# Alternative2.net
KiCad netlist of a schematic drawn in EAGLE
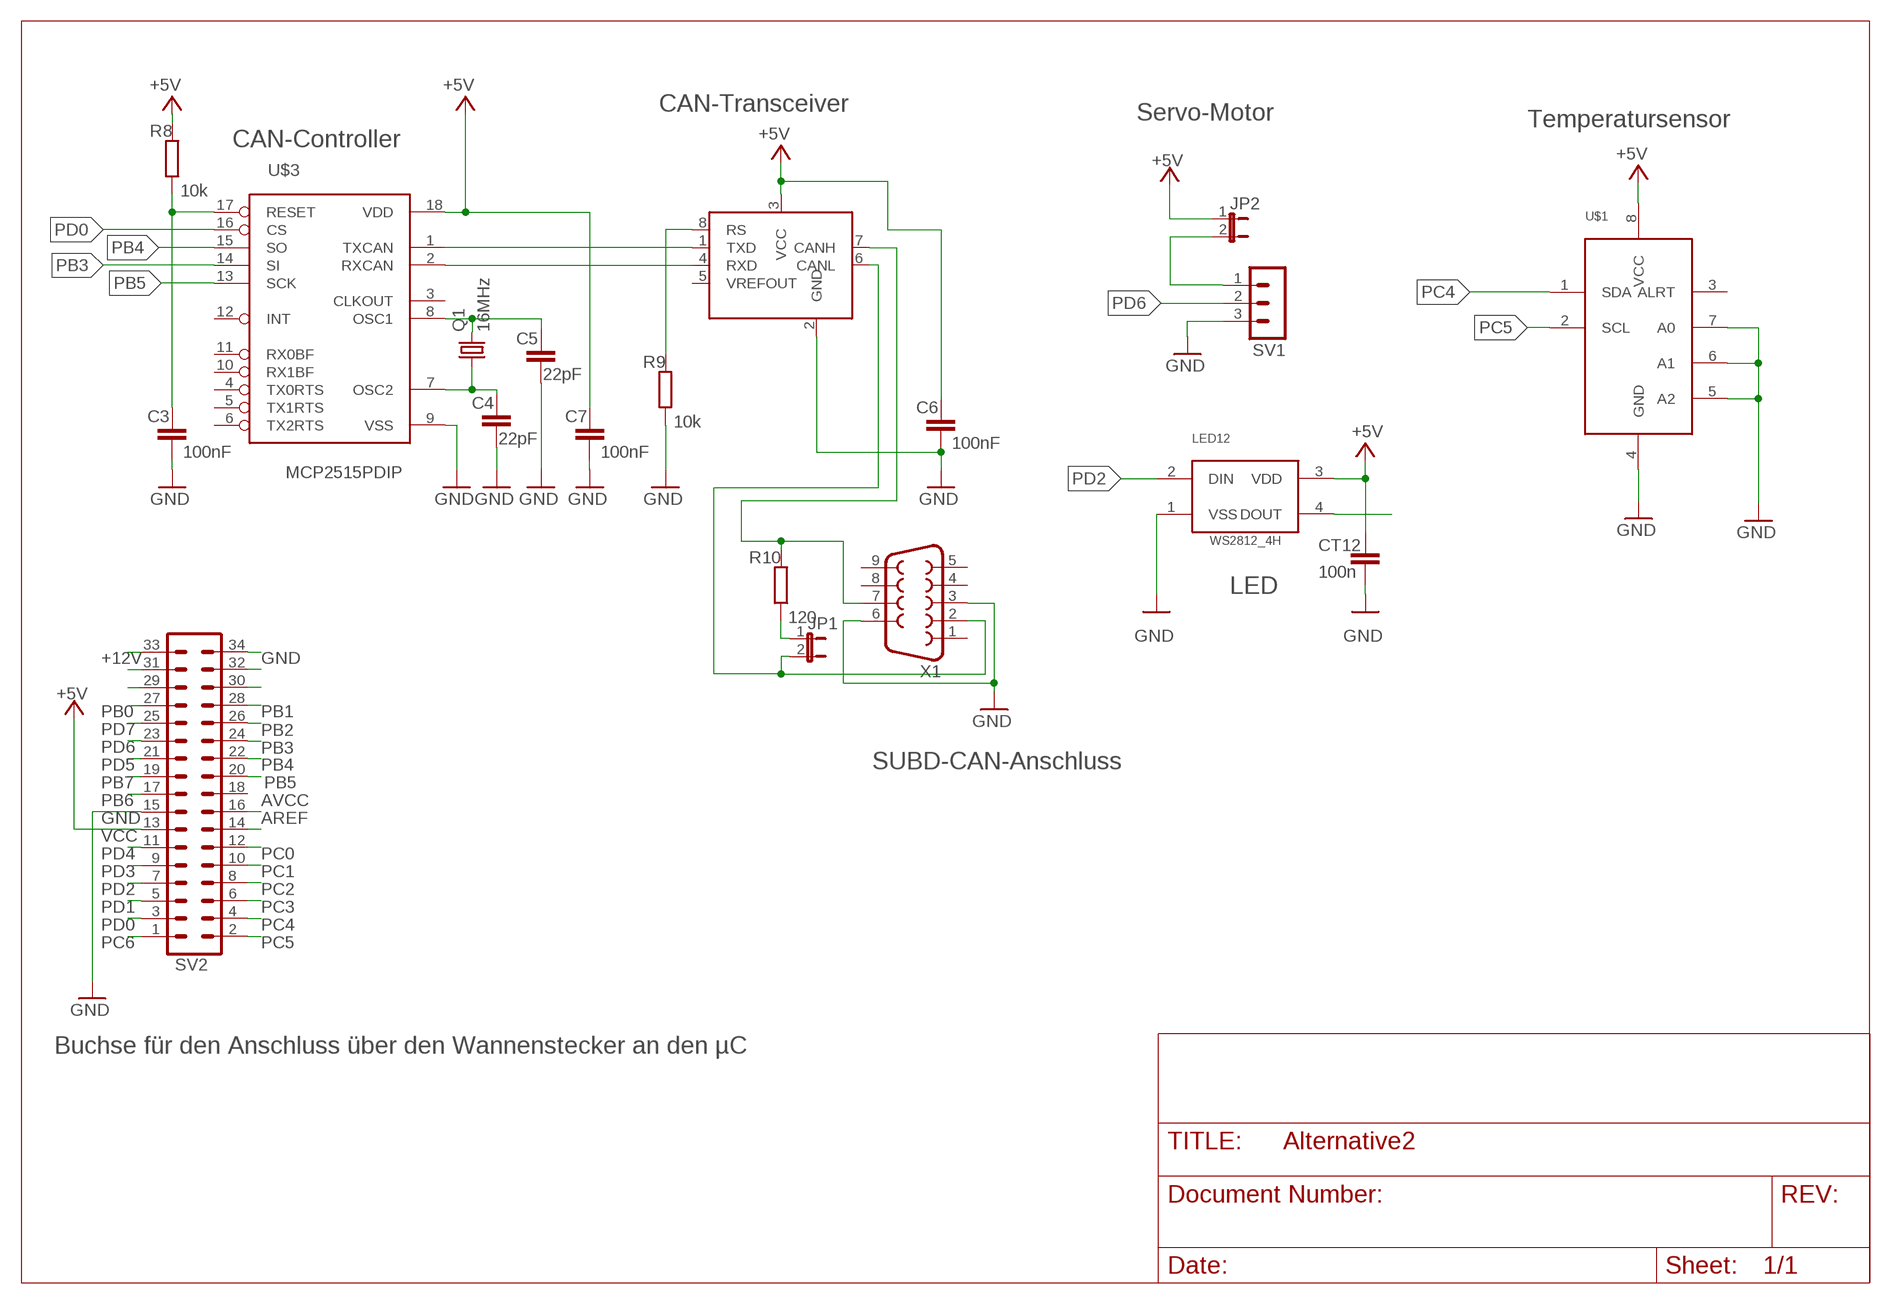
[diagram p0: schematic, sheet 1]

(export (version "E")
  (design (tool "Eeschema 10.0.6"))
  (components
    (comp (ref "C3")
      (value "100nF")
      (footprint "eagle-import:C0805K")
      (libsource (lib "eagle-import") (part "C-EUC0805K"))
    )
    (comp (ref "C4")
      (value "22pF")
      (footprint "eagle-import:C0805K")
      (libsource (lib "eagle-import") (part "C-EUC0805K"))
    )
    (comp (ref "C5")
      (value "22pF")
      (footprint "eagle-import:C0805K")
      (libsource (lib "eagle-import") (part "C-EUC0805K"))
    )
    (comp (ref "C6")
      (value "100nF")
      (footprint "eagle-import:C0805K")
      (libsource (lib "eagle-import") (part "C-EUC0805K"))
    )
    (comp (ref "C7")
      (value "100nF")
      (footprint "eagle-import:C0805K")
      (libsource (lib "eagle-import") (part "C-EUC0805K"))
    )
    (comp (ref "CT12")
      (value "100n")
      (footprint "eagle-import:C0805")
      (libsource (lib "eagle-import") (part "C-EUC0805"))
    )
    (comp (ref "IC2")
      (value "PCA82C251")
      (footprint "eagle-import:SO8")
      (libsource (lib "eagle-import") (part "82C250SMDSMD"))
    )
    (comp (ref "JP1")
      (value "JP1E")
      (footprint "eagle-import:JP1")
      (libsource (lib "eagle-import") (part "JP1E"))
    )
    (comp (ref "JP2")
      (value "JP1E")
      (footprint "eagle-import:JP1")
      (libsource (lib "eagle-import") (part "JP1E"))
    )
    (comp (ref "LED12")
      (value "WS2812_4H")
      (footprint "eagle-import:WS2812_4")
      (libsource (lib "eagle-import") (part "WS2812_4H"))
    )
    (comp (ref "Q1")
      (value "16MHz")
      (footprint "eagle-import:HC49_S")
      (libsource (lib "eagle-import") (part "CRYSTALHC49S"))
    )
    (comp (ref "R8")
      (value "10k")
      (footprint "eagle-import:R0805")
      (libsource (lib "eagle-import") (part "R-EU_R0805"))
    )
    (comp (ref "R9")
      (value "10k")
      (footprint "eagle-import:R0805")
      (libsource (lib "eagle-import") (part "R-EU_R0805"))
    )
    (comp (ref "R10")
      (value "120")
      (footprint "eagle-import:R0805")
      (libsource (lib "eagle-import") (part "R-EU_R0805"))
    )
    (comp (ref "SV1")
      (value "MA03-1")
      (footprint "eagle-import:MA03-1")
      (libsource (lib "eagle-import") (part "MA03-1"))
    )
    (comp (ref "SV2")
      (value "ML34")
      (footprint "eagle-import:ML34")
      (libsource (lib "eagle-import") (part "ML34"))
    )
    (comp (ref "U$1")
      (value "TMP75-SO8")
      (footprint "eagle-import:SO08")
      (libsource (lib "eagle-import") (part "TMP75-SO8"))
    )
    (comp (ref "U$3")
      (value "MCP2515PDIP")
      (footprint "eagle-import:DIL18")
      (libsource (lib "eagle-import") (part "MCP2515PDIP"))
    )
    (comp (ref "X1")
      (value "F09HP")
      (footprint "eagle-import:F09HP")
      (libsource (lib "eagle-import") (part "F09HP"))
    )
  )
  (nets
    (net (code "1") (name "+5V") (class "Default")
      (node (ref "C6") (pin "1") (pinfunction "1_1") (pintype "passive"))
      (node (ref "C7") (pin "1") (pinfunction "1_1") (pintype "passive"))
      (node (ref "CT12") (pin "1") (pinfunction "1_1") (pintype "passive"))
      (node (ref "IC2") (pin "3") (pinfunction "VCC_3") (pintype "power_in"))
      (node (ref "JP2") (pin "1") (pinfunction "1_1") (pintype "passive"))
      (node (ref "LED12") (pin "3") (pinfunction "VDD_3") (pintype "power_in"))
      (node (ref "R8") (pin "2") (pinfunction "2_2") (pintype "passive"))
      (node (ref "SV2") (pin "13") (pinfunction "13_13") (pintype "passive"))
      (node (ref "U$1") (pin "8") (pinfunction "VCC_8") (pintype "power_in"))
      (node (ref "U$3") (pin "18") (pinfunction "VDD_18") (pintype "power_in"))
    )
    (net (code "2") (name "/+12V") (class "Default")
      (node (ref "SV2") (pin "33") (pinfunction "33_33") (pintype "passive"))
    )
    (net (code "3") (name "/AREF") (class "Default")
      (node (ref "SV2") (pin "16") (pinfunction "16_16") (pintype "passive"))
    )
    (net (code "4") (name "/PB0") (class "Default")
      (node (ref "SV2") (pin "27") (pinfunction "27_27") (pintype "passive"))
    )
    (net (code "5") (name "/PB1") (class "Default")
      (node (ref "SV2") (pin "28") (pinfunction "28_28") (pintype "passive"))
    )
    (net (code "6") (name "/PB2") (class "Default")
      (node (ref "SV2") (pin "26") (pinfunction "26_26") (pintype "passive"))
    )
    (net (code "7") (name "/PB6") (class "Default")
      (node (ref "SV2") (pin "17") (pinfunction "17_17") (pintype "passive"))
    )
    (net (code "8") (name "/PB7") (class "Default")
      (node (ref "SV2") (pin "19") (pinfunction "19_19") (pintype "passive"))
    )
    (net (code "9") (name "/PC0") (class "Default")
      (node (ref "SV2") (pin "12") (pinfunction "12_12") (pintype "passive"))
    )
    (net (code "10") (name "/PC1") (class "Default")
      (node (ref "SV2") (pin "10") (pinfunction "10_10") (pintype "passive"))
    )
    (net (code "11") (name "/PC2") (class "Default")
      (node (ref "SV2") (pin "8") (pinfunction "8_8") (pintype "passive"))
    )
    (net (code "12") (name "/PC3") (class "Default")
      (node (ref "SV2") (pin "6") (pinfunction "6_6") (pintype "passive"))
    )
    (net (code "13") (name "/PC6") (class "Default")
      (node (ref "SV2") (pin "1") (pinfunction "1_1") (pintype "passive"))
    )
    (net (code "14") (name "/PD1") (class "Default")
      (node (ref "SV2") (pin "5") (pinfunction "5_5") (pintype "passive"))
    )
    (net (code "15") (name "/PD3") (class "Default")
      (node (ref "SV2") (pin "9") (pinfunction "9_9") (pintype "passive"))
    )
    (net (code "16") (name "/PD4") (class "Default")
      (node (ref "SV2") (pin "11") (pinfunction "11_11") (pintype "passive"))
    )
    (net (code "17") (name "/PD5") (class "Default")
      (node (ref "SV2") (pin "21") (pinfunction "21_21") (pintype "passive"))
    )
    (net (code "18") (name "/PD7") (class "Default")
      (node (ref "SV2") (pin "25") (pinfunction "25_25") (pintype "passive"))
    )
    (net (code "19") (name "GND") (class "Default")
      (node (ref "C3") (pin "2") (pinfunction "2_2") (pintype "passive"))
      (node (ref "C4") (pin "2") (pinfunction "2_2") (pintype "passive"))
      (node (ref "C5") (pin "2") (pinfunction "2_2") (pintype "passive"))
      (node (ref "C6") (pin "2") (pinfunction "2_2") (pintype "passive"))
      (node (ref "C7") (pin "2") (pinfunction "2_2") (pintype "passive"))
      (node (ref "CT12") (pin "2") (pinfunction "2_2") (pintype "passive"))
      (node (ref "IC2") (pin "2") (pinfunction "GND_2") (pintype "power_in"))
      (node (ref "LED12") (pin "1") (pinfunction "VSS_1") (pintype "power_in"))
      (node (ref "R9") (pin "1") (pinfunction "1_1") (pintype "passive"))
      (node (ref "SV1") (pin "3") (pinfunction "3_3") (pintype "passive"))
      (node (ref "SV2") (pin "15") (pinfunction "15_15") (pintype "passive"))
      (node (ref "SV2") (pin "34") (pinfunction "34_34") (pintype "passive"))
      (node (ref "U$1") (pin "4") (pinfunction "GND_4") (pintype "power_in"))
      (node (ref "U$1") (pin "5") (pinfunction "A2_5") (pintype "input"))
      (node (ref "U$1") (pin "6") (pinfunction "A1_6") (pintype "input"))
      (node (ref "U$1") (pin "7") (pinfunction "A0_7") (pintype "input"))
      (node (ref "U$3") (pin "9") (pinfunction "VSS_9") (pintype "power_in"))
      (node (ref "X1") (pin "3") (pinfunction "3_3") (pintype "passive"))
      (node (ref "X1") (pin "6") (pinfunction "6_6") (pintype "passive"))
    )
    (net (code "20") (name "Net-(IC2-CANH)") (class "Default")
      (node (ref "IC2") (pin "7") (pinfunction "CANH_7") (pintype "bidirectional"))
      (node (ref "R10") (pin "2") (pinfunction "2_2") (pintype "passive"))
      (node (ref "X1") (pin "7") (pinfunction "7_7") (pintype "passive"))
    )
    (net (code "21") (name "Net-(IC2-CANL)") (class "Default")
      (node (ref "IC2") (pin "6") (pinfunction "CANL_6") (pintype "bidirectional"))
      (node (ref "JP1") (pin "2") (pinfunction "2_2") (pintype "passive"))
      (node (ref "X1") (pin "2") (pinfunction "2_2") (pintype "passive"))
    )
    (net (code "22") (name "Net-(IC2-RS)") (class "Default")
      (node (ref "IC2") (pin "8") (pinfunction "RS_8") (pintype "input"))
      (node (ref "R9") (pin "2") (pinfunction "2_2") (pintype "passive"))
    )
    (net (code "23") (name "Net-(IC2-RXD)") (class "Default")
      (node (ref "IC2") (pin "4") (pinfunction "RXD_4") (pintype "output"))
      (node (ref "U$3") (pin "2") (pinfunction "RXCAN_2") (pintype "input"))
    )
    (net (code "24") (name "Net-(IC2-TXD)") (class "Default")
      (node (ref "IC2") (pin "1") (pinfunction "TXD_1") (pintype "input"))
      (node (ref "U$3") (pin "1") (pinfunction "TXCAN_1") (pintype "output"))
    )
    (net (code "25") (name "Net-(JP1-Pad1)") (class "Default")
      (node (ref "JP1") (pin "1") (pinfunction "1_1") (pintype "passive"))
      (node (ref "R10") (pin "1") (pinfunction "1_1") (pintype "passive"))
    )
    (net (code "26") (name "Net-(JP2-Pad2)") (class "Default")
      (node (ref "JP2") (pin "2") (pinfunction "2_2") (pintype "passive"))
      (node (ref "SV1") (pin "1") (pinfunction "1_1") (pintype "passive"))
    )
    (net (code "27") (name "Net-(U$3-OSC1)") (class "Default")
      (node (ref "C5") (pin "1") (pinfunction "1_1") (pintype "passive"))
      (node (ref "Q1") (pin "2") (pinfunction "2_2") (pintype "passive"))
      (node (ref "U$3") (pin "8") (pinfunction "OSC1_8") (pintype "input"))
    )
    (net (code "28") (name "Net-(U$3-OSC2)") (class "Default")
      (node (ref "C4") (pin "1") (pinfunction "1_1") (pintype "passive"))
      (node (ref "Q1") (pin "1") (pinfunction "1_1") (pintype "passive"))
      (node (ref "U$3") (pin "7") (pinfunction "OSC2_7") (pintype "input"))
    )
    (net (code "29") (name "Net-(U$3-RESET)") (class "Default")
      (node (ref "C3") (pin "1") (pinfunction "1_1") (pintype "passive"))
      (node (ref "R8") (pin "1") (pinfunction "1_1") (pintype "passive"))
      (node (ref "U$3") (pin "17") (pinfunction "RESET_17") (pintype "input"))
    )
    (net (code "30") (name "PB3") (class "Default")
      (node (ref "SV2") (pin "24") (pinfunction "24_24") (pintype "passive"))
      (node (ref "U$3") (pin "14") (pinfunction "SI_14") (pintype "input"))
    )
    (net (code "31") (name "PB4") (class "Default")
      (node (ref "SV2") (pin "22") (pinfunction "22_22") (pintype "passive"))
      (node (ref "U$3") (pin "15") (pinfunction "SO_15") (pintype "output"))
    )
    (net (code "32") (name "PB5") (class "Default")
      (node (ref "SV2") (pin "20") (pinfunction "20_20") (pintype "passive"))
      (node (ref "U$3") (pin "13") (pinfunction "SCK_13") (pintype "input"))
    )
    (net (code "33") (name "PC4") (class "Default")
      (node (ref "SV2") (pin "4") (pinfunction "4_4") (pintype "passive"))
      (node (ref "U$1") (pin "1") (pinfunction "SDA_1") (pintype "bidirectional"))
    )
    (net (code "34") (name "PC5") (class "Default")
      (node (ref "SV2") (pin "2") (pinfunction "2_2") (pintype "passive"))
      (node (ref "U$1") (pin "2") (pinfunction "SCL_2") (pintype "input"))
    )
    (net (code "35") (name "PD0") (class "Default")
      (node (ref "SV2") (pin "3") (pinfunction "3_3") (pintype "passive"))
      (node (ref "U$3") (pin "16") (pinfunction "CS_16") (pintype "input"))
    )
    (net (code "36") (name "PD2") (class "Default")
      (node (ref "LED12") (pin "2") (pinfunction "DIN_2") (pintype "input"))
      (node (ref "SV2") (pin "7") (pinfunction "7_7") (pintype "passive"))
    )
    (net (code "37") (name "PD6") (class "Default")
      (node (ref "SV1") (pin "2") (pinfunction "2_2") (pintype "passive"))
      (node (ref "SV2") (pin "23") (pinfunction "23_23") (pintype "passive"))
    )
    (net (code "38") (name "unconnected-(IC2-VREFOUT-Pad5)") (class "Default")
      (node (ref "IC2") (pin "5") (pinfunction "VREFOUT_5") (pintype "output"))
    )
    (net (code "39") (name "unconnected-(LED12-DOUT-Pad4)") (class "Default")
      (node (ref "LED12") (pin "4") (pinfunction "DOUT_4") (pintype "output"))
    )
    (net (code "40") (name "unconnected-(SV2-Pad14)") (class "Default")
      (node (ref "SV2") (pin "14") (pinfunction "14_14") (pintype "passive"))
    )
    (net (code "41") (name "unconnected-(SV2-Pad18)") (class "Default")
      (node (ref "SV2") (pin "18") (pinfunction "18_18") (pintype "passive"))
    )
    (net (code "42") (name "unconnected-(SV2-Pad29)") (class "Default")
      (node (ref "SV2") (pin "29") (pinfunction "29_29") (pintype "passive"))
    )
    (net (code "43") (name "unconnected-(SV2-Pad30)") (class "Default")
      (node (ref "SV2") (pin "30") (pinfunction "30_30") (pintype "passive"))
    )
    (net (code "44") (name "unconnected-(SV2-Pad31)") (class "Default")
      (node (ref "SV2") (pin "31") (pinfunction "31_31") (pintype "passive"))
    )
    (net (code "45") (name "unconnected-(SV2-Pad32)") (class "Default")
      (node (ref "SV2") (pin "32") (pinfunction "32_32") (pintype "passive"))
    )
    (net (code "46") (name "unconnected-(U$1-ALRT-Pad3)") (class "Default")
      (node (ref "U$1") (pin "3") (pinfunction "ALRT_3") (pintype "output"))
    )
    (net (code "47") (name "unconnected-(U$3-CLKOUT-Pad3)") (class "Default")
      (node (ref "U$3") (pin "3") (pinfunction "CLKOUT_3") (pintype "output"))
    )
    (net (code "48") (name "unconnected-(U$3-INT-Pad12)") (class "Default")
      (node (ref "U$3") (pin "12") (pinfunction "INT_12") (pintype "input"))
    )
    (net (code "49") (name "unconnected-(U$3-RX0BF-Pad11)") (class "Default")
      (node (ref "U$3") (pin "11") (pinfunction "RX0BF_11") (pintype "input"))
    )
    (net (code "50") (name "unconnected-(U$3-RX1BF-Pad10)") (class "Default")
      (node (ref "U$3") (pin "10") (pinfunction "RX1BF_10") (pintype "input"))
    )
    (net (code "51") (name "unconnected-(U$3-TX0RTS-Pad4)") (class "Default")
      (node (ref "U$3") (pin "4") (pinfunction "TX0RTS_4") (pintype "output"))
    )
    (net (code "52") (name "unconnected-(U$3-TX1RTS-Pad5)") (class "Default")
      (node (ref "U$3") (pin "5") (pinfunction "TX1RTS_5") (pintype "output"))
    )
    (net (code "53") (name "unconnected-(U$3-TX2RTS-Pad6)") (class "Default")
      (node (ref "U$3") (pin "6") (pinfunction "TX2RTS_6") (pintype "output"))
    )
    (net (code "54") (name "unconnected-(X1-Pad1)") (class "Default")
      (node (ref "X1") (pin "1") (pinfunction "1_1") (pintype "passive"))
    )
    (net (code "55") (name "unconnected-(X1-Pad4)") (class "Default")
      (node (ref "X1") (pin "4") (pinfunction "4_4") (pintype "passive"))
    )
    (net (code "56") (name "unconnected-(X1-Pad5)") (class "Default")
      (node (ref "X1") (pin "5") (pinfunction "5_5") (pintype "passive"))
    )
    (net (code "57") (name "unconnected-(X1-Pad8)") (class "Default")
      (node (ref "X1") (pin "8") (pinfunction "8_8") (pintype "passive"))
    )
    (net (code "58") (name "unconnected-(X1-Pad9)") (class "Default")
      (node (ref "X1") (pin "9") (pinfunction "9_9") (pintype "passive"))
    )
  )
)
